# piano555.net
KiCad netlist of a schematic drawn in EAGLE
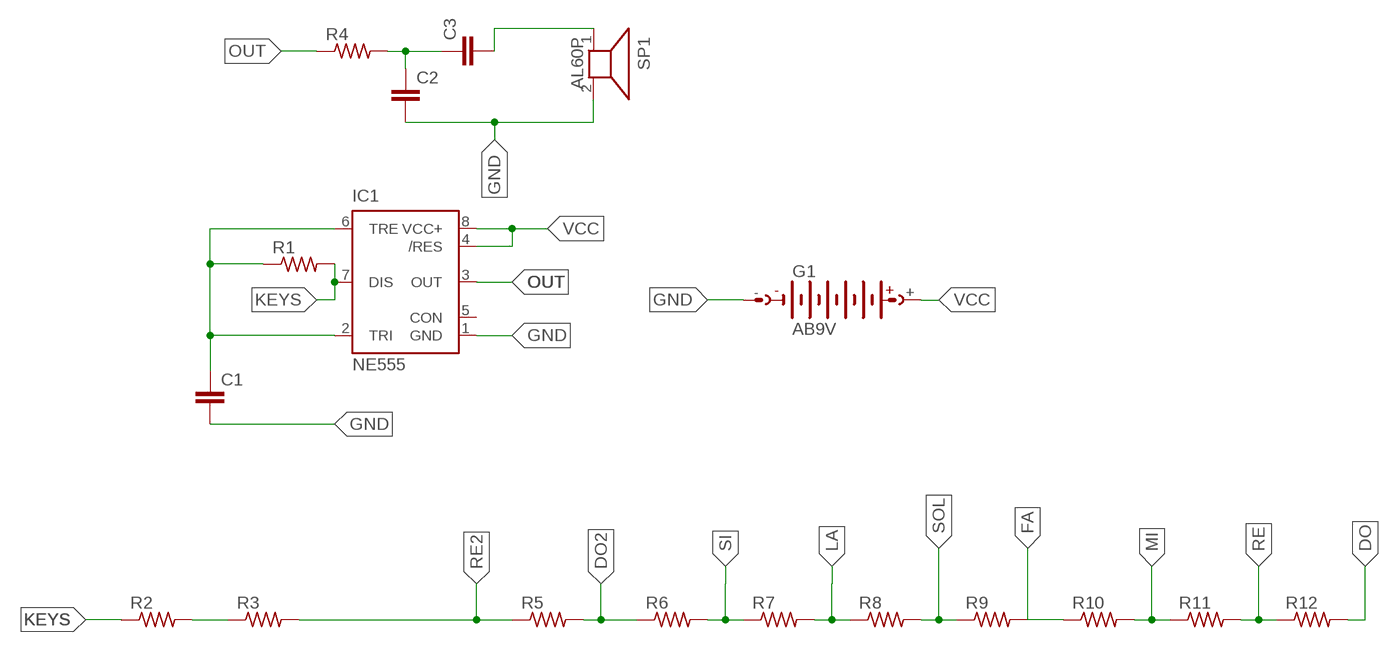
[diagram p0: schematic, sheet 1]

(export (version "E")
  (design (tool "Eeschema 10.0.6"))
  (components
    (comp (ref "C1")
      (value "C-EU025-030X050")
      (footprint "eagle-import:C025-030X050")
      (libsource (lib "eagle-import") (part "C-EU025-030X050"))
    )
    (comp (ref "C2")
      (value "C-EU025-030X050")
      (footprint "eagle-import:C025-030X050")
      (libsource (lib "eagle-import") (part "C-EU025-030X050"))
    )
    (comp (ref "C3")
      (value "C-EU025-030X050")
      (footprint "eagle-import:C025-030X050")
      (libsource (lib "eagle-import") (part "C-EU025-030X050"))
    )
    (comp (ref "G1")
      (value "AB9V")
      (footprint "eagle-import:AB9V")
      (libsource (lib "eagle-import") (part "AB9V"))
    )
    (comp (ref "IC1")
      (value "NE555")
      (footprint "eagle-import:DIL-08")
      (fields (field (name "MF") "Arrow Electronics") (field (name "MPN") "NE555N"))
      (libsource (lib "eagle-import") (part "NE555"))
    )
    (comp (ref "R1")
      (value "R-US_0204/7")
      (footprint "eagle-import:0204_7")
      (libsource (lib "eagle-import") (part "R-US_0204/7"))
    )
    (comp (ref "R2")
      (value "R-US_0204/7")
      (footprint "eagle-import:0204_7")
      (libsource (lib "eagle-import") (part "R-US_0204/7"))
    )
    (comp (ref "R3")
      (value "R-US_0204/7")
      (footprint "eagle-import:0204_7")
      (libsource (lib "eagle-import") (part "R-US_0204/7"))
    )
    (comp (ref "R4")
      (value "R-US_0204/7")
      (footprint "eagle-import:0204_7")
      (libsource (lib "eagle-import") (part "R-US_0204/7"))
    )
    (comp (ref "R5")
      (value "R-US_0204/7")
      (footprint "eagle-import:0204_7")
      (libsource (lib "eagle-import") (part "R-US_0204/7"))
    )
    (comp (ref "R6")
      (value "R-US_0204/7")
      (footprint "eagle-import:0204_7")
      (libsource (lib "eagle-import") (part "R-US_0204/7"))
    )
    (comp (ref "R7")
      (value "R-US_0204/7")
      (footprint "eagle-import:0204_7")
      (libsource (lib "eagle-import") (part "R-US_0204/7"))
    )
    (comp (ref "R8")
      (value "R-US_0204/7")
      (footprint "eagle-import:0204_7")
      (libsource (lib "eagle-import") (part "R-US_0204/7"))
    )
    (comp (ref "R9")
      (value "R-US_0204/7")
      (footprint "eagle-import:0204_7")
      (libsource (lib "eagle-import") (part "R-US_0204/7"))
    )
    (comp (ref "R10")
      (value "R-US_0204/7")
      (footprint "eagle-import:0204_7")
      (libsource (lib "eagle-import") (part "R-US_0204/7"))
    )
    (comp (ref "R11")
      (value "R-US_0204/7")
      (footprint "eagle-import:0204_7")
      (libsource (lib "eagle-import") (part "R-US_0204/7"))
    )
    (comp (ref "R12")
      (value "R-US_0204/7")
      (footprint "eagle-import:0204_7")
      (libsource (lib "eagle-import") (part "R-US_0204/7"))
    )
    (comp (ref "SP1")
      (value "AL60P")
      (footprint "eagle-import:AL60P")
      (libsource (lib "eagle-import") (part "AL60P"))
    )
  )
  (nets
    (net (code "1") (name "DO") (class "Default")
      (node (ref "R12") (pin "2") (pinfunction "2_2") (pintype "passive"))
    )
    (net (code "2") (name "DO2") (class "Default")
      (node (ref "R5") (pin "2") (pinfunction "2_2") (pintype "passive"))
      (node (ref "R6") (pin "1") (pinfunction "1_1") (pintype "passive"))
    )
    (net (code "3") (name "FA") (class "Default")
      (node (ref "R10") (pin "1") (pinfunction "1_1") (pintype "passive"))
      (node (ref "R9") (pin "2") (pinfunction "2_2") (pintype "passive"))
    )
    (net (code "4") (name "GND") (class "Default")
      (node (ref "C1") (pin "2") (pinfunction "2_2") (pintype "passive"))
      (node (ref "C2") (pin "2") (pinfunction "2_2") (pintype "passive"))
      (node (ref "G1") (pin "-") (pinfunction "-_-") (pintype "passive"))
      (node (ref "IC1") (pin "1") (pinfunction "GND_1") (pintype "power_in"))
      (node (ref "SP1") (pin "2") (pinfunction "2_2") (pintype "passive"))
    )
    (net (code "5") (name "KEYS") (class "Default")
      (node (ref "IC1") (pin "7") (pinfunction "DIS_7") (pintype "input"))
      (node (ref "R1") (pin "2") (pinfunction "2_2") (pintype "passive"))
      (node (ref "R2") (pin "1") (pinfunction "1_1") (pintype "passive"))
    )
    (net (code "6") (name "LA") (class "Default")
      (node (ref "R7") (pin "2") (pinfunction "2_2") (pintype "passive"))
      (node (ref "R8") (pin "1") (pinfunction "1_1") (pintype "passive"))
    )
    (net (code "7") (name "MI") (class "Default")
      (node (ref "R10") (pin "2") (pinfunction "2_2") (pintype "passive"))
      (node (ref "R11") (pin "1") (pinfunction "1_1") (pintype "passive"))
    )
    (net (code "8") (name "Net-(C2-Pad1)") (class "Default")
      (node (ref "C2") (pin "1") (pinfunction "1_1") (pintype "passive"))
      (node (ref "C3") (pin "1") (pinfunction "1_1") (pintype "passive"))
      (node (ref "R4") (pin "2") (pinfunction "2_2") (pintype "passive"))
    )
    (net (code "9") (name "Net-(C3-Pad2)") (class "Default")
      (node (ref "C3") (pin "2") (pinfunction "2_2") (pintype "passive"))
      (node (ref "SP1") (pin "1") (pinfunction "1_1") (pintype "passive"))
    )
    (net (code "10") (name "Net-(IC1-TRE)") (class "Default")
      (node (ref "C1") (pin "1") (pinfunction "1_1") (pintype "passive"))
      (node (ref "IC1") (pin "2") (pinfunction "TRI_2") (pintype "input"))
      (node (ref "IC1") (pin "6") (pinfunction "TRE_6") (pintype "input"))
      (node (ref "R1") (pin "1") (pinfunction "1_1") (pintype "passive"))
    )
    (net (code "11") (name "Net-(R2-Pad2)") (class "Default")
      (node (ref "R2") (pin "2") (pinfunction "2_2") (pintype "passive"))
      (node (ref "R3") (pin "1") (pinfunction "1_1") (pintype "passive"))
    )
    (net (code "12") (name "OUT") (class "Default")
      (node (ref "IC1") (pin "3") (pinfunction "OUT_3") (pintype "output"))
      (node (ref "R4") (pin "1") (pinfunction "1_1") (pintype "passive"))
    )
    (net (code "13") (name "RE") (class "Default")
      (node (ref "R11") (pin "2") (pinfunction "2_2") (pintype "passive"))
      (node (ref "R12") (pin "1") (pinfunction "1_1") (pintype "passive"))
    )
    (net (code "14") (name "RE2") (class "Default")
      (node (ref "R3") (pin "2") (pinfunction "2_2") (pintype "passive"))
      (node (ref "R5") (pin "1") (pinfunction "1_1") (pintype "passive"))
    )
    (net (code "15") (name "SI") (class "Default")
      (node (ref "R6") (pin "2") (pinfunction "2_2") (pintype "passive"))
      (node (ref "R7") (pin "1") (pinfunction "1_1") (pintype "passive"))
    )
    (net (code "16") (name "SOL") (class "Default")
      (node (ref "R8") (pin "2") (pinfunction "2_2") (pintype "passive"))
      (node (ref "R9") (pin "1") (pinfunction "1_1") (pintype "passive"))
    )
    (net (code "17") (name "VCC") (class "Default")
      (node (ref "G1") (pin "+") (pinfunction "+_+") (pintype "passive"))
      (node (ref "IC1") (pin "4") (pinfunction "/RES_4") (pintype "input"))
      (node (ref "IC1") (pin "8") (pinfunction "VCC+_8") (pintype "power_in"))
    )
    (net (code "18") (name "unconnected-(IC1-CON-Pad5)") (class "Default")
      (node (ref "IC1") (pin "5") (pinfunction "CON_5") (pintype "input"))
    )
  )
)
